# EnsembleFive.net
KiCad netlist of a schematic drawn in EAGLE
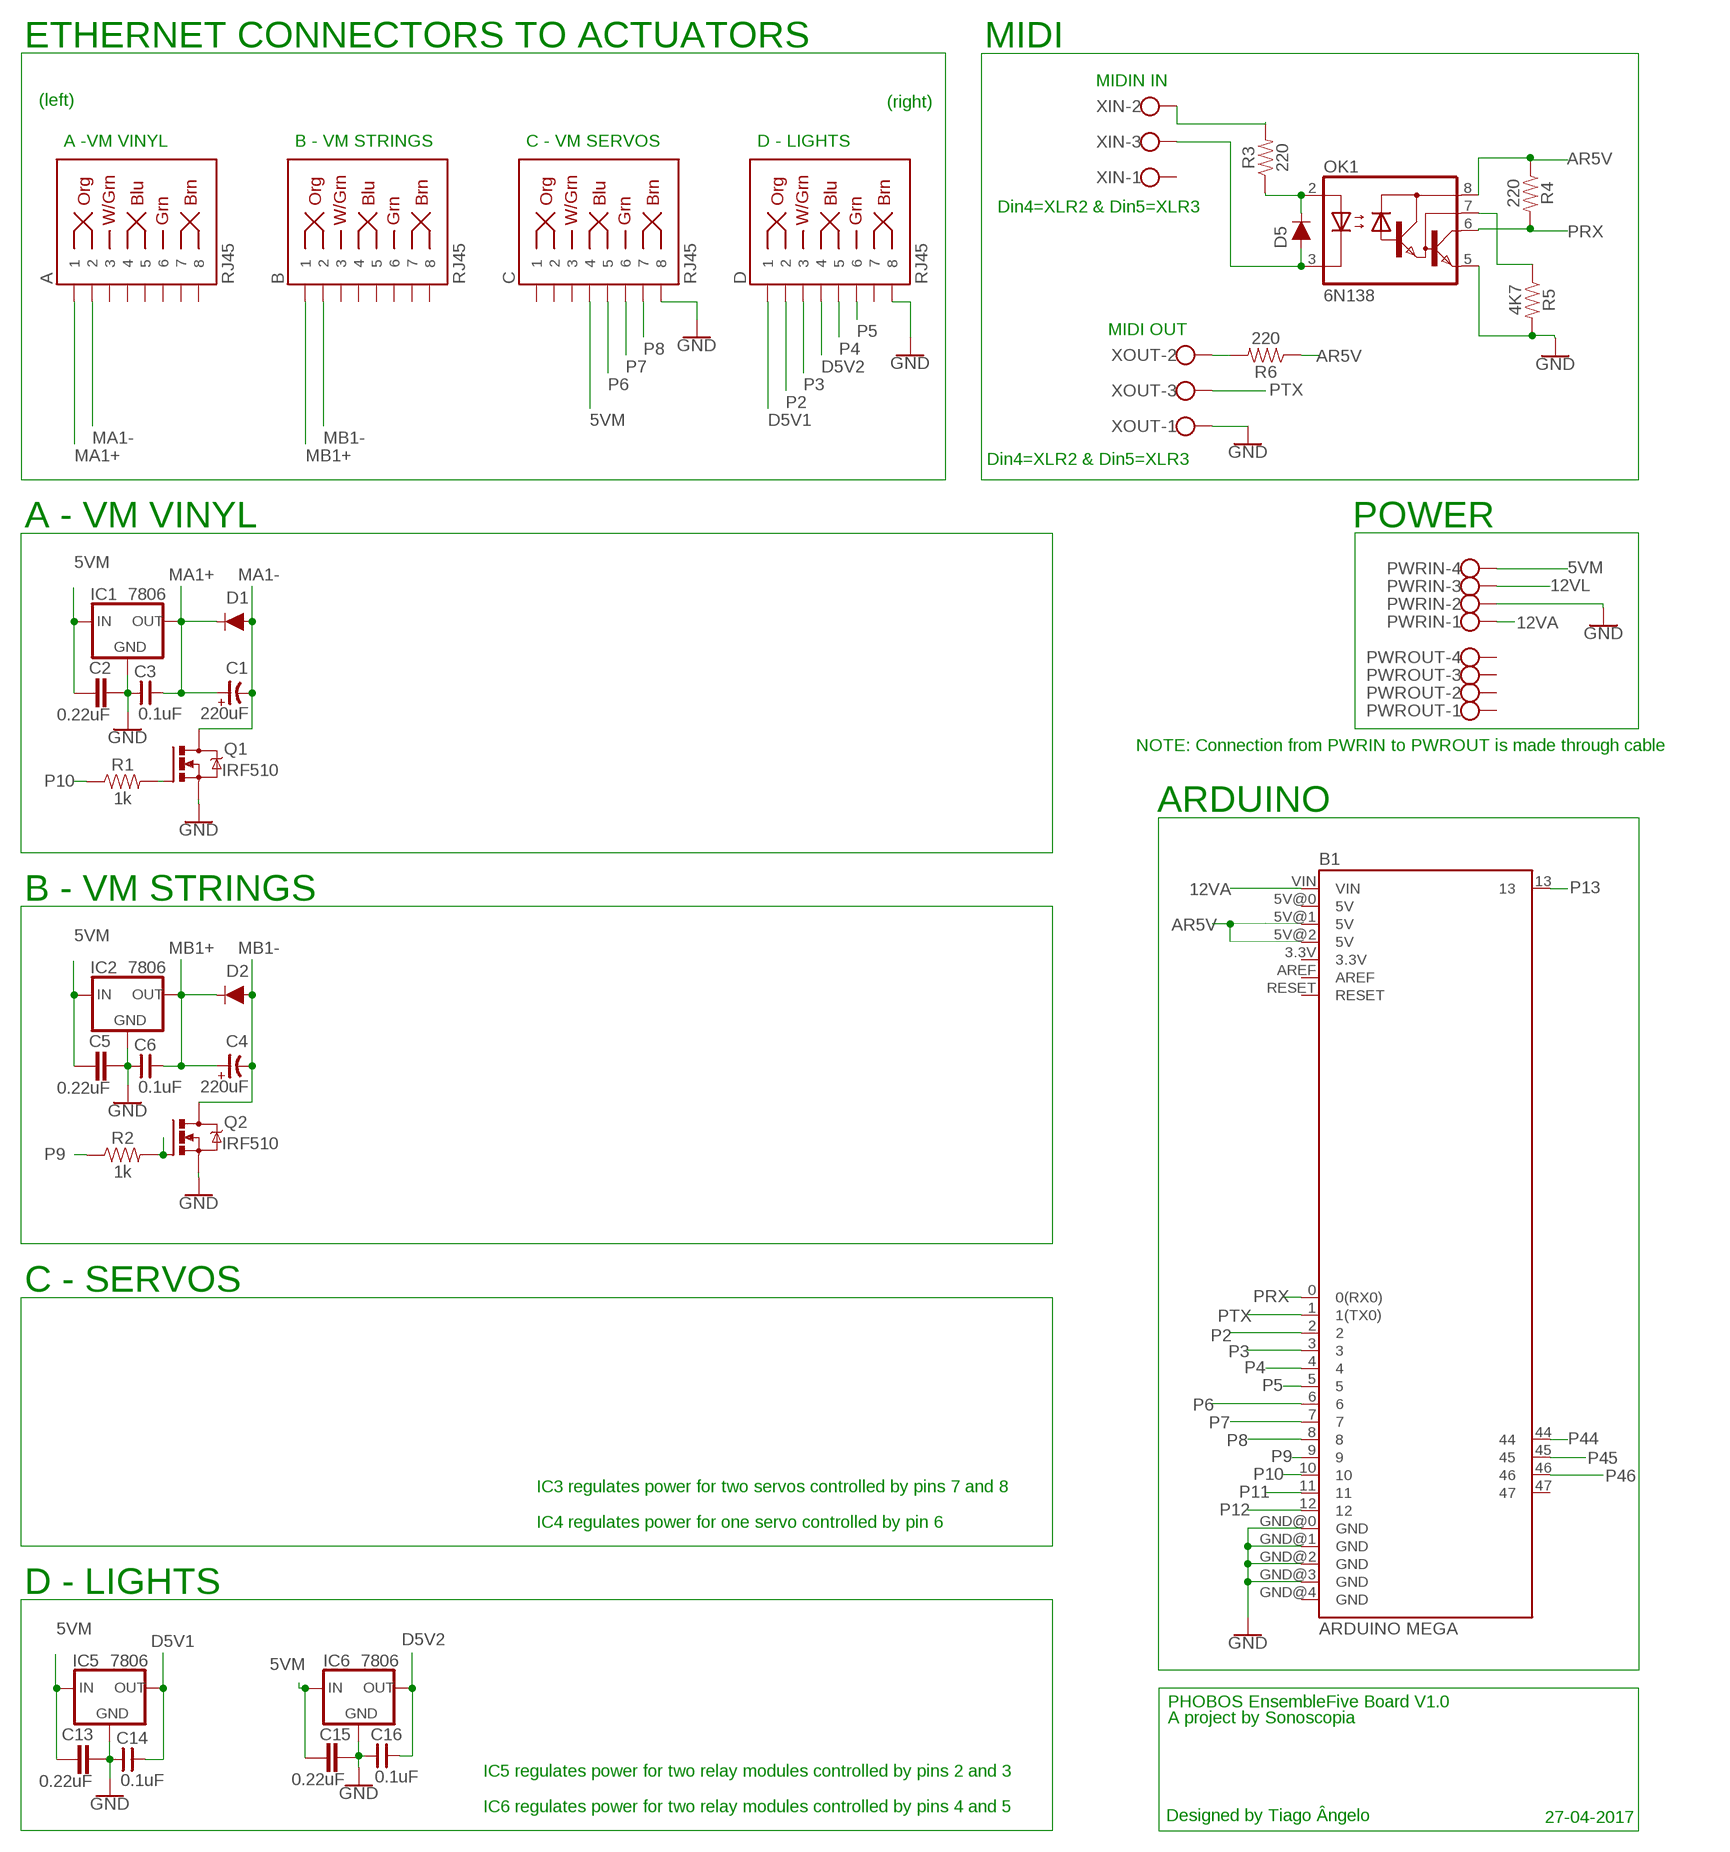
[diagram p0: schematic, sheet 1]

(export (version "E")
  (design (tool "Eeschema 10.0.6"))
  (components
    (comp (ref "A")
      (value "RJ45")
      (footprint "eagle-import:RJ45-8")
      (libsource (lib "eagle-import") (part "RJ45-8"))
    )
    (comp (ref "B")
      (value "RJ45")
      (footprint "eagle-import:RJ45-8")
      (libsource (lib "eagle-import") (part "RJ45-8"))
    )
    (comp (ref "B1")
      (value "ARDUINO MEGA")
      (footprint "eagle-import:ARDUINO_MEGA")
      (libsource (lib "eagle-import") (part "ARDUINO_MEGA_R3FULL"))
    )
    (comp (ref "C")
      (value "RJ45")
      (footprint "eagle-import:RJ45-8")
      (libsource (lib "eagle-import") (part "RJ45-8"))
    )
    (comp (ref "C1")
      (value "220uF")
      (footprint "eagle-import:E-035X080")
      (libsource (lib "eagle-import") (part "CP-E-035X080"))
    )
    (comp (ref "C2")
      (value "0.22uF")
      (footprint "eagle-import:C5B3")
      (libsource (lib "eagle-import") (part "C5/3"))
    )
    (comp (ref "C3")
      (value "0.1uF")
      (footprint "eagle-import:C025-050X025")
      (libsource (lib "eagle-import") (part "CNP-C025-050X025"))
    )
    (comp (ref "C4")
      (value "220uF")
      (footprint "eagle-import:E-035X080")
      (libsource (lib "eagle-import") (part "CP-E-035X080"))
    )
    (comp (ref "C5")
      (value "0.22uF")
      (footprint "eagle-import:C5B3")
      (libsource (lib "eagle-import") (part "C5/3"))
    )
    (comp (ref "C6")
      (value "0.1uF")
      (footprint "eagle-import:C025-050X025")
      (libsource (lib "eagle-import") (part "CNP-C025-050X025"))
    )
    (comp (ref "C13")
      (value "0.22uF")
      (footprint "eagle-import:C5B3")
      (libsource (lib "eagle-import") (part "C5/3"))
    )
    (comp (ref "C14")
      (value "0.1uF")
      (footprint "eagle-import:C025-050X025")
      (libsource (lib "eagle-import") (part "CNP-C025-050X025"))
    )
    (comp (ref "C15")
      (value "0.22uF")
      (footprint "eagle-import:C5B3")
      (libsource (lib "eagle-import") (part "C5/3"))
    )
    (comp (ref "C16")
      (value "0.1uF")
      (footprint "eagle-import:C025-050X025")
      (libsource (lib "eagle-import") (part "CNP-C025-050X025"))
    )
    (comp (ref "D")
      (value "RJ45")
      (footprint "eagle-import:RJ45-8")
      (libsource (lib "eagle-import") (part "RJ45-8"))
    )
    (comp (ref "D1")
      (value "1A/50V/1.1V")
      (footprint "eagle-import:DIODE-1N4001-KIT")
      (libsource (lib "eagle-import") (part "DIODE-KIT2"))
    )
    (comp (ref "D2")
      (value "1A/50V/1.1V")
      (footprint "eagle-import:DIODE-1N4001-KIT")
      (libsource (lib "eagle-import") (part "DIODE-KIT2"))
    )
    (comp (ref "D5")
      (value "200mA/100V/1V")
      (footprint "eagle-import:DIODE-1N4148")
      (libsource (lib "eagle-import") (part "DIODE-1N4148"))
    )
    (comp (ref "IC1")
      (value "7806")
      (footprint "eagle-import:78XXS")
      (libsource (lib "eagle-import") (part "78XXS"))
    )
    (comp (ref "IC2")
      (value "7806")
      (footprint "eagle-import:78XXS")
      (libsource (lib "eagle-import") (part "78XXS"))
    )
    (comp (ref "IC5")
      (value "7806")
      (footprint "eagle-import:78XXS")
      (libsource (lib "eagle-import") (part "78XXS"))
    )
    (comp (ref "IC6")
      (value "7806")
      (footprint "eagle-import:78XXS")
      (libsource (lib "eagle-import") (part "78XXS"))
    )
    (comp (ref "OK1")
      (value "6N138")
      (footprint "eagle-import:DIL08")
      (fields (field (name "MF") "VISHAY/TELEFUNKEN"))
      (libsource (lib "eagle-import") (part "6N138"))
    )
    (comp (ref "PWRIN")
      (value "W237-4")
      (footprint "eagle-import:W237-4")
      (libsource (lib "eagle-import") (part "W237-4"))
    )
    (comp (ref "PWROUT")
      (value "W237-4")
      (footprint "eagle-import:W237-4")
      (libsource (lib "eagle-import") (part "W237-4"))
    )
    (comp (ref "Q1")
      (value "IRF510")
      (footprint "eagle-import:TO220BV")
      (libsource (lib "eagle-import") (part "IRF520"))
    )
    (comp (ref "Q2")
      (value "IRF510")
      (footprint "eagle-import:TO220BV")
      (libsource (lib "eagle-import") (part "IRF520"))
    )
    (comp (ref "R1")
      (value "1k")
      (footprint "eagle-import:AXIAL-0.1")
      (libsource (lib "eagle-import") (part "1KOHM-VERT-1/4W-1%"))
    )
    (comp (ref "R2")
      (value "1k")
      (footprint "eagle-import:AXIAL-0.1")
      (libsource (lib "eagle-import") (part "1KOHM-VERT-1/4W-1%"))
    )
    (comp (ref "R3")
      (value "220")
      (footprint "eagle-import:AXIAL-0.3")
      (libsource (lib "eagle-import") (part "1KOHM-HORIZ-1/4W-5%"))
    )
    (comp (ref "R4")
      (value "220")
      (footprint "eagle-import:AXIAL-0.3")
      (libsource (lib "eagle-import") (part "1KOHM-HORIZ-1/4W-5%"))
    )
    (comp (ref "R5")
      (value "4K7")
      (footprint "eagle-import:AXIAL-0.3")
      (libsource (lib "eagle-import") (part "1KOHM-HORIZ-1/4W-5%"))
    )
    (comp (ref "R6")
      (value "220")
      (footprint "eagle-import:AXIAL-0.3")
      (libsource (lib "eagle-import") (part "1KOHM-HORIZ-1/4W-5%"))
    )
    (comp (ref "XIN")
      (value "W237-103")
      (footprint "eagle-import:W237-103")
      (fields (field (name "MPN") "237-103"))
      (libsource (lib "eagle-import") (part "W237-103"))
    )
    (comp (ref "XOUT")
      (value "W237-103")
      (footprint "eagle-import:W237-103")
      (fields (field (name "MPN") "237-103"))
      (libsource (lib "eagle-import") (part "W237-103"))
    )
  )
  (nets
    (net (code "1") (name "/5VM") (class "Default")
      (node (ref "C") (pin "4") (pinfunction "4_4") (pintype "bidirectional"))
      (node (ref "C13") (pin "1") (pinfunction "1_1") (pintype "passive"))
      (node (ref "C15") (pin "1") (pinfunction "1_1") (pintype "passive"))
      (node (ref "C2") (pin "1") (pinfunction "1_1") (pintype "passive"))
      (node (ref "C5") (pin "1") (pinfunction "1_1") (pintype "passive"))
      (node (ref "IC1") (pin "IN") (pinfunction "IN_IN") (pintype "input"))
      (node (ref "IC2") (pin "IN") (pinfunction "IN_IN") (pintype "input"))
      (node (ref "IC5") (pin "IN") (pinfunction "IN_IN") (pintype "input"))
      (node (ref "IC6") (pin "IN") (pinfunction "IN_IN") (pintype "input"))
      (node (ref "PWRIN") (pin "4") (pinfunction "KL_4") (pintype "passive"))
    )
    (net (code "2") (name "/12VA") (class "Default")
      (node (ref "B1") (pin "VIN") (pinfunction "VIN_VIN") (pintype "bidirectional"))
      (node (ref "PWRIN") (pin "1") (pinfunction "KL_1") (pintype "passive"))
    )
    (net (code "3") (name "/12VL") (class "Default")
      (node (ref "PWRIN") (pin "3") (pinfunction "KL_3") (pintype "passive"))
    )
    (net (code "4") (name "/AR5V") (class "Default")
      (node (ref "B1") (pin "5V@1") (pinfunction "5V_5V@1") (pintype "bidirectional"))
      (node (ref "B1") (pin "5V@2") (pinfunction "5V_5V@2") (pintype "bidirectional"))
      (node (ref "OK1") (pin "8") (pinfunction "VCC_8") (pintype "passive"))
      (node (ref "R4") (pin "P$1") (pinfunction "1_P$1") (pintype "passive"))
      (node (ref "R6") (pin "P$1") (pinfunction "1_P$1") (pintype "passive"))
    )
    (net (code "5") (name "/D5V1") (class "Default")
      (node (ref "C14") (pin "2") (pinfunction "2_2") (pintype "passive"))
      (node (ref "D") (pin "1") (pinfunction "1_1") (pintype "bidirectional"))
      (node (ref "IC5") (pin "OUT") (pinfunction "OUT_OUT") (pintype "passive"))
    )
    (net (code "6") (name "/D5V2") (class "Default")
      (node (ref "C16") (pin "2") (pinfunction "2_2") (pintype "passive"))
      (node (ref "D") (pin "4") (pinfunction "4_4") (pintype "bidirectional"))
      (node (ref "IC6") (pin "OUT") (pinfunction "OUT_OUT") (pintype "passive"))
    )
    (net (code "7") (name "/MA1+") (class "Default")
      (node (ref "A") (pin "1") (pinfunction "1_1") (pintype "bidirectional"))
      (node (ref "C1") (pin "+") (pinfunction "+_+") (pintype "passive"))
      (node (ref "C3") (pin "2") (pinfunction "2_2") (pintype "passive"))
      (node (ref "D1") (pin "C") (pinfunction "C_C") (pintype "passive"))
      (node (ref "IC1") (pin "OUT") (pinfunction "OUT_OUT") (pintype "passive"))
    )
    (net (code "8") (name "/MA1-") (class "Default")
      (node (ref "A") (pin "2") (pinfunction "2_2") (pintype "bidirectional"))
      (node (ref "C1") (pin "-") (pinfunction "-_-") (pintype "passive"))
      (node (ref "D1") (pin "A") (pinfunction "A_A") (pintype "passive"))
      (node (ref "Q1") (pin "D") (pinfunction "D_D") (pintype "passive"))
    )
    (net (code "9") (name "/MB1+") (class "Default")
      (node (ref "B") (pin "1") (pinfunction "1_1") (pintype "bidirectional"))
      (node (ref "C4") (pin "+") (pinfunction "+_+") (pintype "passive"))
      (node (ref "C6") (pin "2") (pinfunction "2_2") (pintype "passive"))
      (node (ref "D2") (pin "C") (pinfunction "C_C") (pintype "passive"))
      (node (ref "IC2") (pin "OUT") (pinfunction "OUT_OUT") (pintype "passive"))
    )
    (net (code "10") (name "/MB1-") (class "Default")
      (node (ref "B") (pin "2") (pinfunction "2_2") (pintype "bidirectional"))
      (node (ref "C4") (pin "-") (pinfunction "-_-") (pintype "passive"))
      (node (ref "D2") (pin "A") (pinfunction "A_A") (pintype "passive"))
      (node (ref "Q2") (pin "D") (pinfunction "D_D") (pintype "passive"))
    )
    (net (code "11") (name "/P2") (class "Default")
      (node (ref "B1") (pin "2") (pinfunction "2_2") (pintype "bidirectional"))
      (node (ref "D") (pin "2") (pinfunction "2_2") (pintype "bidirectional"))
    )
    (net (code "12") (name "/P3") (class "Default")
      (node (ref "B1") (pin "3") (pinfunction "3_3") (pintype "bidirectional"))
      (node (ref "D") (pin "3") (pinfunction "3_3") (pintype "bidirectional"))
    )
    (net (code "13") (name "/P4") (class "Default")
      (node (ref "B1") (pin "4") (pinfunction "4_4") (pintype "bidirectional"))
      (node (ref "D") (pin "5") (pinfunction "5_5") (pintype "bidirectional"))
    )
    (net (code "14") (name "/P5") (class "Default")
      (node (ref "B1") (pin "5") (pinfunction "5_5") (pintype "bidirectional"))
      (node (ref "D") (pin "6") (pinfunction "6_6") (pintype "bidirectional"))
    )
    (net (code "15") (name "/P6") (class "Default")
      (node (ref "B1") (pin "6") (pinfunction "6_6") (pintype "bidirectional"))
      (node (ref "C") (pin "5") (pinfunction "5_5") (pintype "bidirectional"))
    )
    (net (code "16") (name "/P7") (class "Default")
      (node (ref "B1") (pin "7") (pinfunction "7_7") (pintype "bidirectional"))
      (node (ref "C") (pin "6") (pinfunction "6_6") (pintype "bidirectional"))
    )
    (net (code "17") (name "/P8") (class "Default")
      (node (ref "B1") (pin "8") (pinfunction "8_8") (pintype "bidirectional"))
      (node (ref "C") (pin "7") (pinfunction "7_7") (pintype "bidirectional"))
    )
    (net (code "18") (name "/P9") (class "Default")
      (node (ref "B1") (pin "9") (pinfunction "9_9") (pintype "bidirectional"))
      (node (ref "R2") (pin "P$1") (pinfunction "1_P$1") (pintype "passive"))
    )
    (net (code "19") (name "/P10") (class "Default")
      (node (ref "B1") (pin "10") (pinfunction "10_10") (pintype "bidirectional"))
      (node (ref "R1") (pin "P$1") (pinfunction "1_P$1") (pintype "passive"))
    )
    (net (code "20") (name "/P11") (class "Default")
      (node (ref "B1") (pin "11") (pinfunction "11_11") (pintype "bidirectional"))
    )
    (net (code "21") (name "/P12") (class "Default")
      (node (ref "B1") (pin "12") (pinfunction "12_12") (pintype "bidirectional"))
    )
    (net (code "22") (name "/P13") (class "Default")
      (node (ref "B1") (pin "13") (pinfunction "13_13") (pintype "bidirectional"))
    )
    (net (code "23") (name "/P44") (class "Default")
      (node (ref "B1") (pin "44") (pinfunction "44_44") (pintype "bidirectional"))
    )
    (net (code "24") (name "/P45") (class "Default")
      (node (ref "B1") (pin "45") (pinfunction "45_45") (pintype "bidirectional"))
    )
    (net (code "25") (name "/P46") (class "Default")
      (node (ref "B1") (pin "46") (pinfunction "46_46") (pintype "bidirectional"))
    )
    (net (code "26") (name "/PRX") (class "Default")
      (node (ref "B1") (pin "0") (pinfunction "0(RX0)_0") (pintype "bidirectional"))
      (node (ref "OK1") (pin "6") (pinfunction "VO_6") (pintype "passive"))
      (node (ref "R4") (pin "P$2") (pinfunction "2_P$2") (pintype "passive"))
    )
    (net (code "27") (name "/PTX") (class "Default")
      (node (ref "B1") (pin "1") (pinfunction "1(TX0)_1") (pintype "bidirectional"))
      (node (ref "XOUT") (pin "3") (pinfunction "KL_3") (pintype "passive"))
    )
    (net (code "28") (name "GND") (class "Default")
      (node (ref "B1") (pin "GND@0") (pinfunction "GND_GND@0") (pintype "bidirectional"))
      (node (ref "B1") (pin "GND@1") (pinfunction "GND_GND@1") (pintype "bidirectional"))
      (node (ref "B1") (pin "GND@2") (pinfunction "GND_GND@2") (pintype "bidirectional"))
      (node (ref "B1") (pin "GND@3") (pinfunction "GND_GND@3") (pintype "bidirectional"))
      (node (ref "C") (pin "8") (pinfunction "8_8") (pintype "bidirectional"))
      (node (ref "C13") (pin "2") (pinfunction "2_2") (pintype "passive"))
      (node (ref "C14") (pin "1") (pinfunction "1_1") (pintype "passive"))
      (node (ref "C15") (pin "2") (pinfunction "2_2") (pintype "passive"))
      (node (ref "C16") (pin "1") (pinfunction "1_1") (pintype "passive"))
      (node (ref "C2") (pin "2") (pinfunction "2_2") (pintype "passive"))
      (node (ref "C3") (pin "1") (pinfunction "1_1") (pintype "passive"))
      (node (ref "C5") (pin "2") (pinfunction "2_2") (pintype "passive"))
      (node (ref "C6") (pin "1") (pinfunction "1_1") (pintype "passive"))
      (node (ref "D") (pin "8") (pinfunction "8_8") (pintype "bidirectional"))
      (node (ref "IC1") (pin "GND") (pinfunction "GND_GND") (pintype "input"))
      (node (ref "IC2") (pin "GND") (pinfunction "GND_GND") (pintype "input"))
      (node (ref "IC5") (pin "GND") (pinfunction "GND_GND") (pintype "input"))
      (node (ref "IC6") (pin "GND") (pinfunction "GND_GND") (pintype "input"))
      (node (ref "OK1") (pin "5") (pinfunction "GND_5") (pintype "passive"))
      (node (ref "PWRIN") (pin "2") (pinfunction "KL_2") (pintype "passive"))
      (node (ref "Q1") (pin "S") (pinfunction "S_S") (pintype "passive"))
      (node (ref "Q2") (pin "S") (pinfunction "S_S") (pintype "passive"))
      (node (ref "R5") (pin "P$2") (pinfunction "2_P$2") (pintype "passive"))
      (node (ref "XOUT") (pin "1") (pinfunction "KL_1") (pintype "passive"))
    )
    (net (code "29") (name "Net-(OK1-A)") (class "Default")
      (node (ref "D5") (pin "C") (pinfunction "C_C") (pintype "passive"))
      (node (ref "OK1") (pin "2") (pinfunction "A_2") (pintype "passive"))
      (node (ref "R3") (pin "P$1") (pinfunction "1_P$1") (pintype "passive"))
    )
    (net (code "30") (name "Net-(OK1-C)") (class "Default")
      (node (ref "D5") (pin "A") (pinfunction "A_A") (pintype "passive"))
      (node (ref "OK1") (pin "3") (pinfunction "C_3") (pintype "passive"))
      (node (ref "XIN") (pin "3") (pinfunction "KL_3") (pintype "passive"))
    )
    (net (code "31") (name "Net-(OK1-VB)") (class "Default")
      (node (ref "OK1") (pin "7") (pinfunction "VB_7") (pintype "passive"))
      (node (ref "R5") (pin "P$1") (pinfunction "1_P$1") (pintype "passive"))
    )
    (net (code "32") (name "Net-(R1-2)") (class "Default")
      (node (ref "Q1") (pin "G") (pinfunction "G_G") (pintype "passive"))
      (node (ref "R1") (pin "P$2") (pinfunction "2_P$2") (pintype "passive"))
    )
    (net (code "33") (name "Net-(R2-2)") (class "Default")
      (node (ref "Q2") (pin "G") (pinfunction "G_G") (pintype "passive"))
      (node (ref "R2") (pin "P$2") (pinfunction "2_P$2") (pintype "passive"))
    )
    (net (code "34") (name "Net-(R3-2)") (class "Default")
      (node (ref "R3") (pin "P$2") (pinfunction "2_P$2") (pintype "passive"))
      (node (ref "XIN") (pin "2") (pinfunction "KL_2") (pintype "passive"))
    )
    (net (code "35") (name "Net-(R6-2)") (class "Default")
      (node (ref "R6") (pin "P$2") (pinfunction "2_P$2") (pintype "passive"))
      (node (ref "XOUT") (pin "2") (pinfunction "KL_2") (pintype "passive"))
    )
    (net (code "36") (name "unconnected-(A-Pad3)") (class "Default")
      (node (ref "A") (pin "3") (pinfunction "3_3") (pintype "bidirectional"))
    )
    (net (code "37") (name "unconnected-(A-Pad4)") (class "Default")
      (node (ref "A") (pin "4") (pinfunction "4_4") (pintype "bidirectional"))
    )
    (net (code "38") (name "unconnected-(A-Pad5)") (class "Default")
      (node (ref "A") (pin "5") (pinfunction "5_5") (pintype "bidirectional"))
    )
    (net (code "39") (name "unconnected-(A-Pad6)") (class "Default")
      (node (ref "A") (pin "6") (pinfunction "6_6") (pintype "bidirectional"))
    )
    (net (code "40") (name "unconnected-(A-Pad7)") (class "Default")
      (node (ref "A") (pin "7") (pinfunction "7_7") (pintype "bidirectional"))
    )
    (net (code "41") (name "unconnected-(A-Pad8)") (class "Default")
      (node (ref "A") (pin "8") (pinfunction "8_8") (pintype "bidirectional"))
    )
    (net (code "42") (name "unconnected-(B-Pad3)") (class "Default")
      (node (ref "B") (pin "3") (pinfunction "3_3") (pintype "bidirectional"))
    )
    (net (code "43") (name "unconnected-(B-Pad4)") (class "Default")
      (node (ref "B") (pin "4") (pinfunction "4_4") (pintype "bidirectional"))
    )
    (net (code "44") (name "unconnected-(B-Pad5)") (class "Default")
      (node (ref "B") (pin "5") (pinfunction "5_5") (pintype "bidirectional"))
    )
    (net (code "45") (name "unconnected-(B-Pad6)") (class "Default")
      (node (ref "B") (pin "6") (pinfunction "6_6") (pintype "bidirectional"))
    )
    (net (code "46") (name "unconnected-(B-Pad7)") (class "Default")
      (node (ref "B") (pin "7") (pinfunction "7_7") (pintype "bidirectional"))
    )
    (net (code "47") (name "unconnected-(B-Pad8)") (class "Default")
      (node (ref "B") (pin "8") (pinfunction "8_8") (pintype "bidirectional"))
    )
    (net (code "48") (name "unconnected-(B1-5V-Pad5V@0)") (class "Default")
      (node (ref "B1") (pin "5V@0") (pinfunction "5V_5V@0") (pintype "bidirectional"))
    )
    (net (code "49") (name "unconnected-(B1-GND-PadGND@4)") (class "Default")
      (node (ref "B1") (pin "GND@4") (pinfunction "GND_GND@4") (pintype "bidirectional"))
    )
    (net (code "50") (name "unconnected-(B1-Pad3.3V)") (class "Default")
      (node (ref "B1") (pin "3.3V") (pinfunction "3.3V_3.3V") (pintype "bidirectional"))
    )
    (net (code "51") (name "unconnected-(B1-Pad47)") (class "Default")
      (node (ref "B1") (pin "47") (pinfunction "47_47") (pintype "bidirectional"))
    )
    (net (code "52") (name "unconnected-(B1-PadAREF)") (class "Default")
      (node (ref "B1") (pin "AREF") (pinfunction "AREF_AREF") (pintype "bidirectional"))
    )
    (net (code "53") (name "unconnected-(B1-PadRESET)") (class "Default")
      (node (ref "B1") (pin "RESET") (pinfunction "RESET_RESET") (pintype "bidirectional"))
    )
    (net (code "54") (name "unconnected-(C-Pad1)") (class "Default")
      (node (ref "C") (pin "1") (pinfunction "1_1") (pintype "bidirectional"))
    )
    (net (code "55") (name "unconnected-(C-Pad2)") (class "Default")
      (node (ref "C") (pin "2") (pinfunction "2_2") (pintype "bidirectional"))
    )
    (net (code "56") (name "unconnected-(C-Pad3)") (class "Default")
      (node (ref "C") (pin "3") (pinfunction "3_3") (pintype "bidirectional"))
    )
    (net (code "57") (name "unconnected-(D-Pad7)") (class "Default")
      (node (ref "D") (pin "7") (pinfunction "7_7") (pintype "bidirectional"))
    )
    (net (code "58") (name "unconnected-(PWROUTA-KL-Pad1)") (class "Default")
      (node (ref "PWROUT") (pin "1") (pinfunction "KL_1") (pintype "passive"))
    )
    (net (code "59") (name "unconnected-(PWROUTB-KL-Pad2)") (class "Default")
      (node (ref "PWROUT") (pin "2") (pinfunction "KL_2") (pintype "passive"))
    )
    (net (code "60") (name "unconnected-(PWROUTC-KL-Pad3)") (class "Default")
      (node (ref "PWROUT") (pin "3") (pinfunction "KL_3") (pintype "passive"))
    )
    (net (code "61") (name "unconnected-(PWROUTD-KL-Pad4)") (class "Default")
      (node (ref "PWROUT") (pin "4") (pinfunction "KL_4") (pintype "passive"))
    )
    (net (code "62") (name "unconnected-(XINA-KL-Pad1)") (class "Default")
      (node (ref "XIN") (pin "1") (pinfunction "KL_1") (pintype "passive"))
    )
  )
)
